# attinier85-batty-shield-mk-2_3.net
KiCad netlist of a schematic drawn in EAGLE
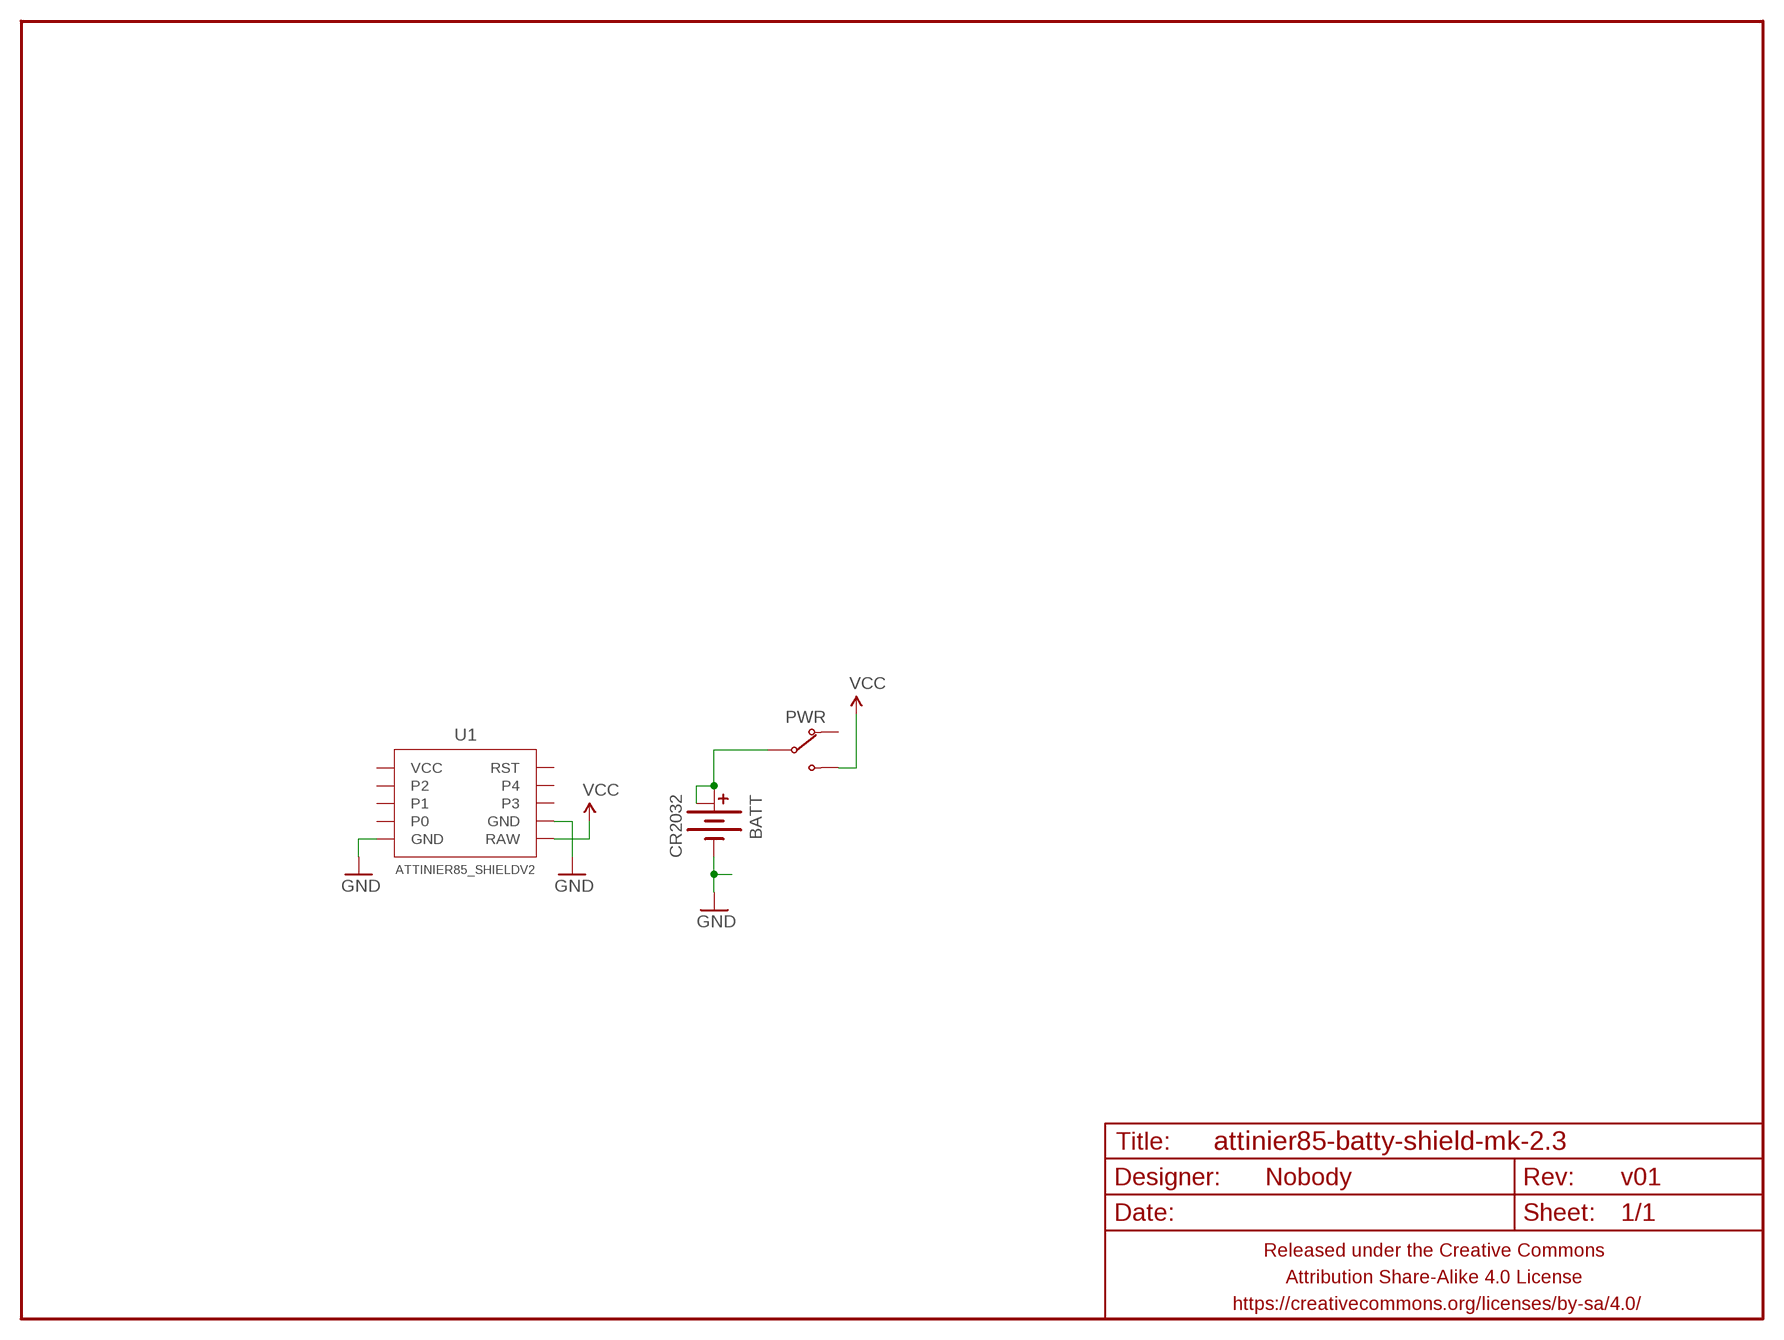
[diagram p0: schematic, sheet 1]

(export (version "E")
  (design (tool "Eeschema 10.0.6"))
  (components
    (comp (ref "BATT")
      (value "CR2032")
      (footprint "eagle-import:BATTCON_20MM_MINE")
      (libsource (lib "eagle-import") (part "BATTERY-COINCR2032_SMD"))
    )
    (comp (ref "FRAME1")
      (value "FRAME-LETTERNO_PACKAGE")
      (footprint "eagle-import:DUMMY")
      (fields (field (name "DESIGNER") "Nobody"))
      (libsource (lib "eagle-import") (part "FRAME-LETTERNO_PACKAGE"))
    )
    (comp (ref "PWR")
      (value "SWITCH-SPDTPTH-RA-2MM")
      (footprint "eagle-import:SPDT-RA-2MM")
      (libsource (lib "eagle-import") (part "SWITCH-SPDTPTH-RA-2MM"))
    )
    (comp (ref "U1")
      (value "ATTINIER85_SHIELDV2")
      (footprint "eagle-import:ATTINIER85_SHIELD_V2")
      (libsource (lib "eagle-import") (part "ATTINIER85_SHIELDV2"))
    )
  )
  (nets
    (net (code "1") (name "GND") (class "Default")
      (node (ref "BATT") (pin "BOTTOM") (pinfunction "-_BOTTOM") (pintype "bidirectional"))
      (node (ref "U1") (pin "GND@1") (pinfunction "GND_GND@1") (pintype "bidirectional"))
      (node (ref "U1") (pin "GND@2") (pinfunction "GND_GND@2") (pintype "bidirectional"))
    )
    (net (code "2") (name "Net-(BATT-+)") (class "Default")
      (node (ref "BATT") (pin "TOP@1") (pinfunction "+_TOP@1") (pintype "bidirectional"))
      (node (ref "BATT") (pin "TOP@2") (pinfunction "+1_TOP@2") (pintype "bidirectional"))
      (node (ref "PWR") (pin "2") (pinfunction "COM_2") (pintype "passive"))
    )
    (net (code "3") (name "VCC") (class "Default")
      (node (ref "PWR") (pin "3") (pinfunction "NO_3") (pintype "passive"))
      (node (ref "U1") (pin "RAW") (pinfunction "RAW_RAW") (pintype "bidirectional"))
    )
    (net (code "4") (name "unconnected-(PWR-NC-Pad1)") (class "Default")
      (node (ref "PWR") (pin "1") (pinfunction "NC_1") (pintype "passive"))
    )
    (net (code "5") (name "unconnected-(U1-P0-Pad0)") (class "Default")
      (node (ref "U1") (pin "0") (pinfunction "P0_0") (pintype "bidirectional"))
    )
    (net (code "6") (name "unconnected-(U1-P1-Pad1)") (class "Default")
      (node (ref "U1") (pin "1") (pinfunction "P1_1") (pintype "bidirectional"))
    )
    (net (code "7") (name "unconnected-(U1-P2-Pad2)") (class "Default")
      (node (ref "U1") (pin "2") (pinfunction "P2_2") (pintype "bidirectional"))
    )
    (net (code "8") (name "unconnected-(U1-P3-Pad3)") (class "Default")
      (node (ref "U1") (pin "3") (pinfunction "P3_3") (pintype "bidirectional"))
    )
    (net (code "9") (name "unconnected-(U1-P4-Pad4)") (class "Default")
      (node (ref "U1") (pin "4") (pinfunction "P4_4") (pintype "bidirectional"))
    )
    (net (code "10") (name "unconnected-(U1-PadRST)") (class "Default")
      (node (ref "U1") (pin "RST") (pinfunction "RST_RST") (pintype "bidirectional"))
    )
    (net (code "11") (name "unconnected-(U1-PadVCC)") (class "Default")
      (node (ref "U1") (pin "VCC") (pinfunction "VCC_VCC") (pintype "bidirectional"))
    )
  )
)
